# main-v3.net
KiCad netlist of a schematic drawn in EAGLE
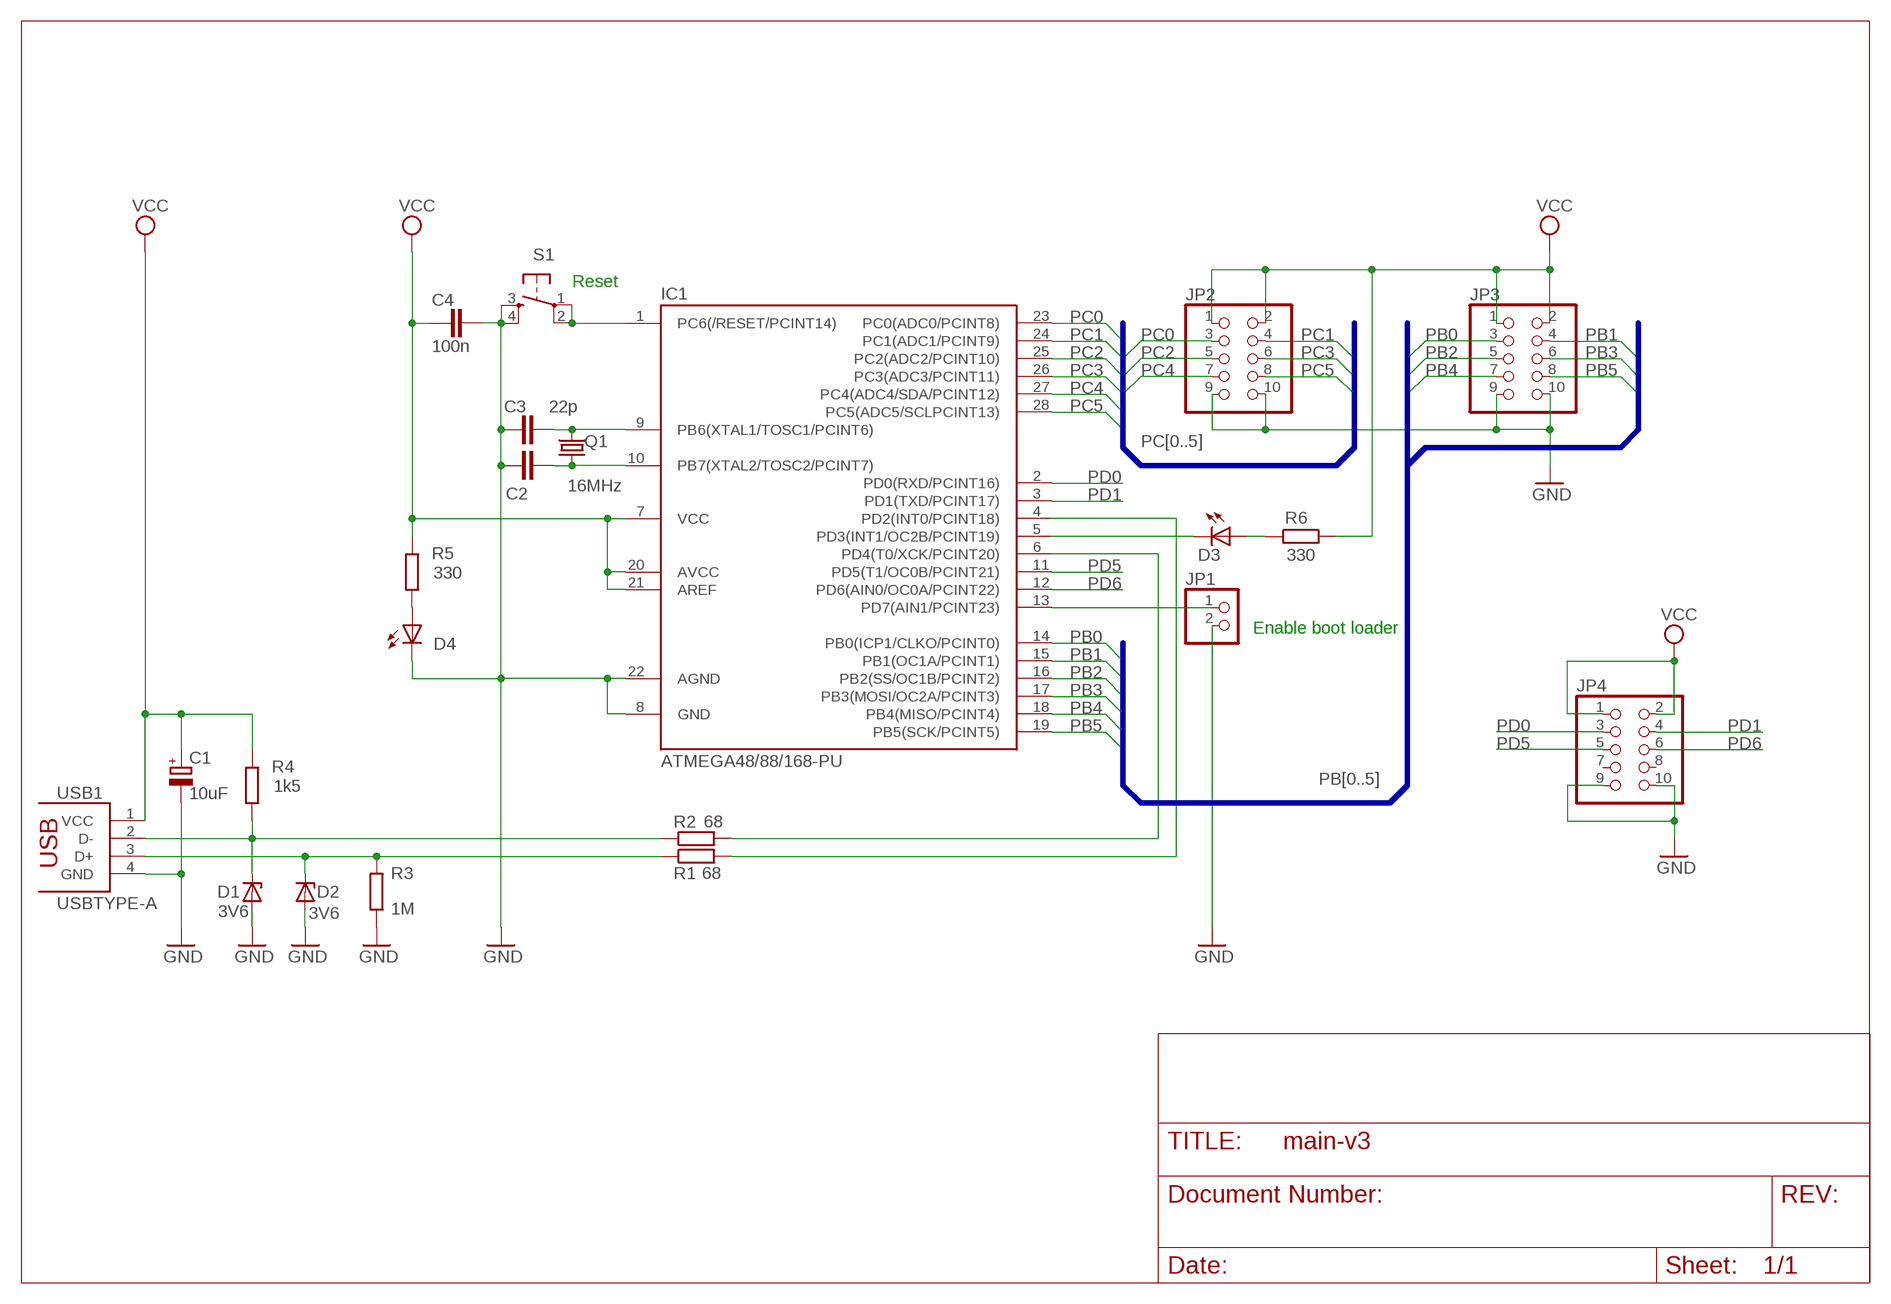
[diagram p0: schematic, sheet 1]

(export (version "E")
  (design (tool "Eeschema 10.0.6"))
  (components
    (comp (ref "C1")
      (value "10uF")
      (footprint "eagle-import:E2,5-6E")
      (libsource (lib "eagle-import") (part "CPOL-EUE2,5-6E"))
    )
    (comp (ref "C2")
      (value "22p")
      (footprint "eagle-import:C025-024X044")
      (libsource (lib "eagle-import") (part "C-EU025-024X044"))
    )
    (comp (ref "C3")
      (value "22p")
      (footprint "eagle-import:C025-024X044")
      (libsource (lib "eagle-import") (part "C-EU025-024X044"))
    )
    (comp (ref "C4")
      (value "100n")
      (footprint "eagle-import:C050-024X044")
      (libsource (lib "eagle-import") (part "C-EU050-024X044"))
    )
    (comp (ref "D1")
      (value "3V6")
      (footprint "eagle-import:DO34Z7")
      (libsource (lib "eagle-import") (part "ZENER-DIODEDO34-7"))
    )
    (comp (ref "D2")
      (value "3V6")
      (footprint "eagle-import:DO34Z7")
      (libsource (lib "eagle-import") (part "ZENER-DIODEDO34-7"))
    )
    (comp (ref "D3")
      (value "LED3MM")
      (footprint "eagle-import:LED3MM")
      (libsource (lib "eagle-import") (part "LED3MM"))
    )
    (comp (ref "D4")
      (value "LED3MM")
      (footprint "eagle-import:LED3MM")
      (libsource (lib "eagle-import") (part "LED3MM"))
    )
    (comp (ref "IC1")
      (value "ATMEGA48/88/168-PU")
      (footprint "eagle-import:DIL28-3")
      (libsource (lib "eagle-import") (part "ATMEGA48/88/168-PU"))
    )
    (comp (ref "JP1")
      (value "PINHD-1X2")
      (footprint "eagle-import:1X02")
      (libsource (lib "eagle-import") (part "PINHD-1X2"))
    )
    (comp (ref "JP2")
      (value "HEADER-2X5")
      (footprint "eagle-import:2X05")
      (libsource (lib "eagle-import") (part "HEADER-2X5"))
    )
    (comp (ref "JP3")
      (value "HEADER-2X5")
      (footprint "eagle-import:2X05")
      (libsource (lib "eagle-import") (part "HEADER-2X5"))
    )
    (comp (ref "JP4")
      (value "HEADER-2X5")
      (footprint "eagle-import:2X05")
      (libsource (lib "eagle-import") (part "HEADER-2X5"))
    )
    (comp (ref "Q1")
      (value "16MHz")
      (footprint "eagle-import:HC49_S")
      (libsource (lib "eagle-import") (part "CRYSTALHC49S"))
    )
    (comp (ref "R1")
      (value "68")
      (footprint "eagle-import:0207_10")
      (libsource (lib "eagle-import") (part "R-EU_0207/10"))
    )
    (comp (ref "R2")
      (value "68")
      (footprint "eagle-import:0207_10")
      (libsource (lib "eagle-import") (part "R-EU_0207/10"))
    )
    (comp (ref "R3")
      (value "1M")
      (footprint "eagle-import:0207_10")
      (libsource (lib "eagle-import") (part "R-EU_0207/10"))
    )
    (comp (ref "R4")
      (value "1k5")
      (footprint "eagle-import:0207_10")
      (libsource (lib "eagle-import") (part "R-EU_0207/10"))
    )
    (comp (ref "R5")
      (value "330")
      (footprint "eagle-import:0207_10")
      (libsource (lib "eagle-import") (part "R-EU_0207/10"))
    )
    (comp (ref "R6")
      (value "330")
      (footprint "eagle-import:0207_10")
      (libsource (lib "eagle-import") (part "R-EU_0207/10"))
    )
    (comp (ref "S1")
      (value "DTS-6")
      (footprint "eagle-import:DTS-6")
      (libsource (lib "eagle-import") (part "DTS-6"))
    )
    (comp (ref "USB1")
      (value "USBTYPE-A")
      (footprint "eagle-import:USBTYPE-A")
      (libsource (lib "eagle-import") (part "USBTYPE-A"))
    )
  )
  (nets
    (net (code "1") (name "/PB0") (class "Default")
      (node (ref "IC1") (pin "14") (pinfunction "PB0(ICP1/CLKO/PCINT0)_14") (pintype "bidirectional"))
      (node (ref "JP3") (pin "3") (pinfunction "3_3") (pintype "passive"))
    )
    (net (code "2") (name "/PB1") (class "Default")
      (node (ref "IC1") (pin "15") (pinfunction "PB1(OC1A/PCINT1)_15") (pintype "bidirectional"))
      (node (ref "JP3") (pin "4") (pinfunction "4_4") (pintype "passive"))
    )
    (net (code "3") (name "/PB2") (class "Default")
      (node (ref "IC1") (pin "16") (pinfunction "PB2(SS/OC1B/PCINT2)_16") (pintype "bidirectional"))
      (node (ref "JP3") (pin "5") (pinfunction "5_5") (pintype "passive"))
    )
    (net (code "4") (name "/PB3") (class "Default")
      (node (ref "IC1") (pin "17") (pinfunction "PB3(MOSI/OC2A/PCINT3)_17") (pintype "bidirectional"))
      (node (ref "JP3") (pin "6") (pinfunction "6_6") (pintype "passive"))
    )
    (net (code "5") (name "/PB4") (class "Default")
      (node (ref "IC1") (pin "18") (pinfunction "PB4(MISO/PCINT4)_18") (pintype "bidirectional"))
      (node (ref "JP3") (pin "7") (pinfunction "7_7") (pintype "passive"))
    )
    (net (code "6") (name "/PB5") (class "Default")
      (node (ref "IC1") (pin "19") (pinfunction "PB5(SCK/PCINT5)_19") (pintype "bidirectional"))
      (node (ref "JP3") (pin "8") (pinfunction "8_8") (pintype "passive"))
    )
    (net (code "8") (name "/PC0") (class "Default")
      (node (ref "IC1") (pin "23") (pinfunction "PC0(ADC0/PCINT8)_23") (pintype "bidirectional"))
      (node (ref "JP2") (pin "3") (pinfunction "3_3") (pintype "passive"))
    )
    (net (code "9") (name "/PC1") (class "Default")
      (node (ref "IC1") (pin "24") (pinfunction "PC1(ADC1/PCINT9)_24") (pintype "bidirectional"))
      (node (ref "JP2") (pin "4") (pinfunction "4_4") (pintype "passive"))
    )
    (net (code "10") (name "/PC2") (class "Default")
      (node (ref "IC1") (pin "25") (pinfunction "PC2(ADC2/PCINT10)_25") (pintype "bidirectional"))
      (node (ref "JP2") (pin "5") (pinfunction "5_5") (pintype "passive"))
    )
    (net (code "11") (name "/PC3") (class "Default")
      (node (ref "IC1") (pin "26") (pinfunction "PC3(ADC3/PCINT11)_26") (pintype "bidirectional"))
      (node (ref "JP2") (pin "6") (pinfunction "6_6") (pintype "passive"))
    )
    (net (code "12") (name "/PC4") (class "Default")
      (node (ref "IC1") (pin "27") (pinfunction "PC4(ADC4/SDA/PCINT12)_27") (pintype "bidirectional"))
      (node (ref "JP2") (pin "7") (pinfunction "7_7") (pintype "passive"))
    )
    (net (code "13") (name "/PC5") (class "Default")
      (node (ref "IC1") (pin "28") (pinfunction "PC5(ADC5/SCLPCINT13)_28") (pintype "bidirectional"))
      (node (ref "JP2") (pin "8") (pinfunction "8_8") (pintype "passive"))
    )
    (net (code "15") (name "/PD0") (class "Default")
      (node (ref "IC1") (pin "2") (pinfunction "PD0(RXD/PCINT16)_2") (pintype "bidirectional"))
      (node (ref "JP4") (pin "3") (pinfunction "3_3") (pintype "passive"))
    )
    (net (code "16") (name "/PD1") (class "Default")
      (node (ref "IC1") (pin "3") (pinfunction "PD1(TXD/PCINT17)_3") (pintype "bidirectional"))
      (node (ref "JP4") (pin "4") (pinfunction "4_4") (pintype "passive"))
    )
    (net (code "17") (name "/PD5") (class "Default")
      (node (ref "IC1") (pin "11") (pinfunction "PD5(T1/OC0B/PCINT21)_11") (pintype "bidirectional"))
      (node (ref "JP4") (pin "5") (pinfunction "5_5") (pintype "passive"))
    )
    (net (code "18") (name "/PD6") (class "Default")
      (node (ref "IC1") (pin "12") (pinfunction "PD6(AIN0/OC0A/PCINT22)_12") (pintype "bidirectional"))
      (node (ref "JP4") (pin "6") (pinfunction "6_6") (pintype "passive"))
    )
    (net (code "19") (name "GND") (class "Default")
      (node (ref "C1") (pin "-") (pinfunction "-_-") (pintype "passive"))
      (node (ref "C2") (pin "1") (pinfunction "1_1") (pintype "passive"))
      (node (ref "C3") (pin "1") (pinfunction "1_1") (pintype "passive"))
      (node (ref "C4") (pin "2") (pinfunction "2_2") (pintype "passive"))
      (node (ref "D1") (pin "A") (pinfunction "A_A") (pintype "passive"))
      (node (ref "D2") (pin "A") (pinfunction "A_A") (pintype "passive"))
      (node (ref "D4") (pin "K") (pinfunction "C_K") (pintype "passive"))
      (node (ref "IC1") (pin "22") (pinfunction "AGND_22") (pintype "power_in"))
      (node (ref "IC1") (pin "8") (pinfunction "GND_8") (pintype "power_in"))
      (node (ref "JP1") (pin "2") (pinfunction "2_2") (pintype "passive"))
      (node (ref "JP2") (pin "10") (pinfunction "10_10") (pintype "passive"))
      (node (ref "JP2") (pin "9") (pinfunction "9_9") (pintype "passive"))
      (node (ref "JP3") (pin "10") (pinfunction "10_10") (pintype "passive"))
      (node (ref "JP3") (pin "9") (pinfunction "9_9") (pintype "passive"))
      (node (ref "JP4") (pin "10") (pinfunction "10_10") (pintype "passive"))
      (node (ref "JP4") (pin "9") (pinfunction "9_9") (pintype "passive"))
      (node (ref "R3") (pin "1") (pinfunction "1_1") (pintype "passive"))
      (node (ref "S1") (pin "3") (pinfunction "3_3") (pintype "passive"))
      (node (ref "S1") (pin "4") (pinfunction "4_4") (pintype "passive"))
      (node (ref "USB1") (pin "4") (pinfunction "GND_4") (pintype "power_in"))
    )
    (net (code "20") (name "Net-(D3-C)") (class "Default")
      (node (ref "D3") (pin "K") (pinfunction "C_K") (pintype "passive"))
      (node (ref "IC1") (pin "5") (pinfunction "PD3(INT1/OC2B/PCINT19)_5") (pintype "bidirectional"))
    )
    (net (code "21") (name "Net-(D3-PadA)") (class "Default")
      (node (ref "D3") (pin "A") (pinfunction "A_A") (pintype "passive"))
      (node (ref "R6") (pin "2") (pinfunction "2_2") (pintype "passive"))
    )
    (net (code "22") (name "Net-(D4-PadA)") (class "Default")
      (node (ref "D4") (pin "A") (pinfunction "A_A") (pintype "passive"))
      (node (ref "R5") (pin "2") (pinfunction "2_2") (pintype "passive"))
    )
    (net (code "23") (name "Net-(IC1-PB6(XTAL1{slash}TOSC1{slash}PCINT6))") (class "Default")
      (node (ref "C3") (pin "2") (pinfunction "2_2") (pintype "passive"))
      (node (ref "IC1") (pin "9") (pinfunction "PB6(XTAL1/TOSC1/PCINT6)_9") (pintype "bidirectional"))
      (node (ref "Q1") (pin "2") (pinfunction "2_2") (pintype "passive"))
    )
    (net (code "24") (name "Net-(IC1-PB7(XTAL2{slash}TOSC2{slash}PCINT7))") (class "Default")
      (node (ref "C2") (pin "2") (pinfunction "2_2") (pintype "passive"))
      (node (ref "IC1") (pin "10") (pinfunction "PB7(XTAL2/TOSC2/PCINT7)_10") (pintype "bidirectional"))
      (node (ref "Q1") (pin "1") (pinfunction "1_1") (pintype "passive"))
    )
    (net (code "25") (name "Net-(IC1-PC6({slash}RESET{slash}PCINT14))") (class "Default")
      (node (ref "IC1") (pin "1") (pinfunction "PC6(/RESET/PCINT14)_1") (pintype "bidirectional"))
      (node (ref "S1") (pin "1") (pinfunction "1_1") (pintype "passive"))
      (node (ref "S1") (pin "2") (pinfunction "2_2") (pintype "passive"))
    )
    (net (code "26") (name "Net-(IC1-PD2(INT0{slash}PCINT18))") (class "Default")
      (node (ref "IC1") (pin "4") (pinfunction "PD2(INT0/PCINT18)_4") (pintype "bidirectional"))
      (node (ref "R1") (pin "2") (pinfunction "2_2") (pintype "passive"))
    )
    (net (code "27") (name "Net-(IC1-PD4(T0{slash}XCK{slash}PCINT20))") (class "Default")
      (node (ref "IC1") (pin "6") (pinfunction "PD4(T0/XCK/PCINT20)_6") (pintype "bidirectional"))
      (node (ref "R2") (pin "2") (pinfunction "2_2") (pintype "passive"))
    )
    (net (code "28") (name "Net-(IC1-PD7(AIN1{slash}PCINT23))") (class "Default")
      (node (ref "IC1") (pin "13") (pinfunction "PD7(AIN1/PCINT23)_13") (pintype "bidirectional"))
      (node (ref "JP1") (pin "1") (pinfunction "1_1") (pintype "passive"))
    )
    (net (code "29") (name "Net-(USB1-D+)") (class "Default")
      (node (ref "D2") (pin "C") (pinfunction "C_C") (pintype "passive"))
      (node (ref "R1") (pin "1") (pinfunction "1_1") (pintype "passive"))
      (node (ref "R3") (pin "2") (pinfunction "2_2") (pintype "passive"))
      (node (ref "USB1") (pin "3") (pinfunction "D+_3") (pintype "bidirectional"))
    )
    (net (code "30") (name "Net-(USB1-D-)") (class "Default")
      (node (ref "D1") (pin "C") (pinfunction "C_C") (pintype "passive"))
      (node (ref "R2") (pin "1") (pinfunction "1_1") (pintype "passive"))
      (node (ref "R4") (pin "2") (pinfunction "2_2") (pintype "passive"))
      (node (ref "USB1") (pin "2") (pinfunction "D-_2") (pintype "bidirectional"))
    )
    (net (code "31") (name "VCC") (class "Default")
      (node (ref "C1") (pin "+") (pinfunction "+_+") (pintype "passive"))
      (node (ref "C4") (pin "1") (pinfunction "1_1") (pintype "passive"))
      (node (ref "IC1") (pin "20") (pinfunction "AVCC_20") (pintype "passive"))
      (node (ref "IC1") (pin "21") (pinfunction "AREF_21") (pintype "passive"))
      (node (ref "IC1") (pin "7") (pinfunction "VCC_7") (pintype "power_in"))
      (node (ref "JP2") (pin "1") (pinfunction "1_1") (pintype "passive"))
      (node (ref "JP2") (pin "2") (pinfunction "2_2") (pintype "passive"))
      (node (ref "JP3") (pin "1") (pinfunction "1_1") (pintype "passive"))
      (node (ref "JP3") (pin "2") (pinfunction "2_2") (pintype "passive"))
      (node (ref "JP4") (pin "1") (pinfunction "1_1") (pintype "passive"))
      (node (ref "JP4") (pin "2") (pinfunction "2_2") (pintype "passive"))
      (node (ref "R4") (pin "1") (pinfunction "1_1") (pintype "passive"))
      (node (ref "R5") (pin "1") (pinfunction "1_1") (pintype "passive"))
      (node (ref "R6") (pin "1") (pinfunction "1_1") (pintype "passive"))
      (node (ref "USB1") (pin "1") (pinfunction "VCC_1") (pintype "power_in"))
    )
    (net (code "32") (name "unconnected-(JP4-Pad7)") (class "Default")
      (node (ref "JP4") (pin "7") (pinfunction "7_7") (pintype "passive"))
    )
    (net (code "33") (name "unconnected-(JP4-Pad8)") (class "Default")
      (node (ref "JP4") (pin "8") (pinfunction "8_8") (pintype "passive"))
    )
  )
)
